# Arduino_extension_connectors.net
KiCad netlist of a schematic drawn in Altium Designer
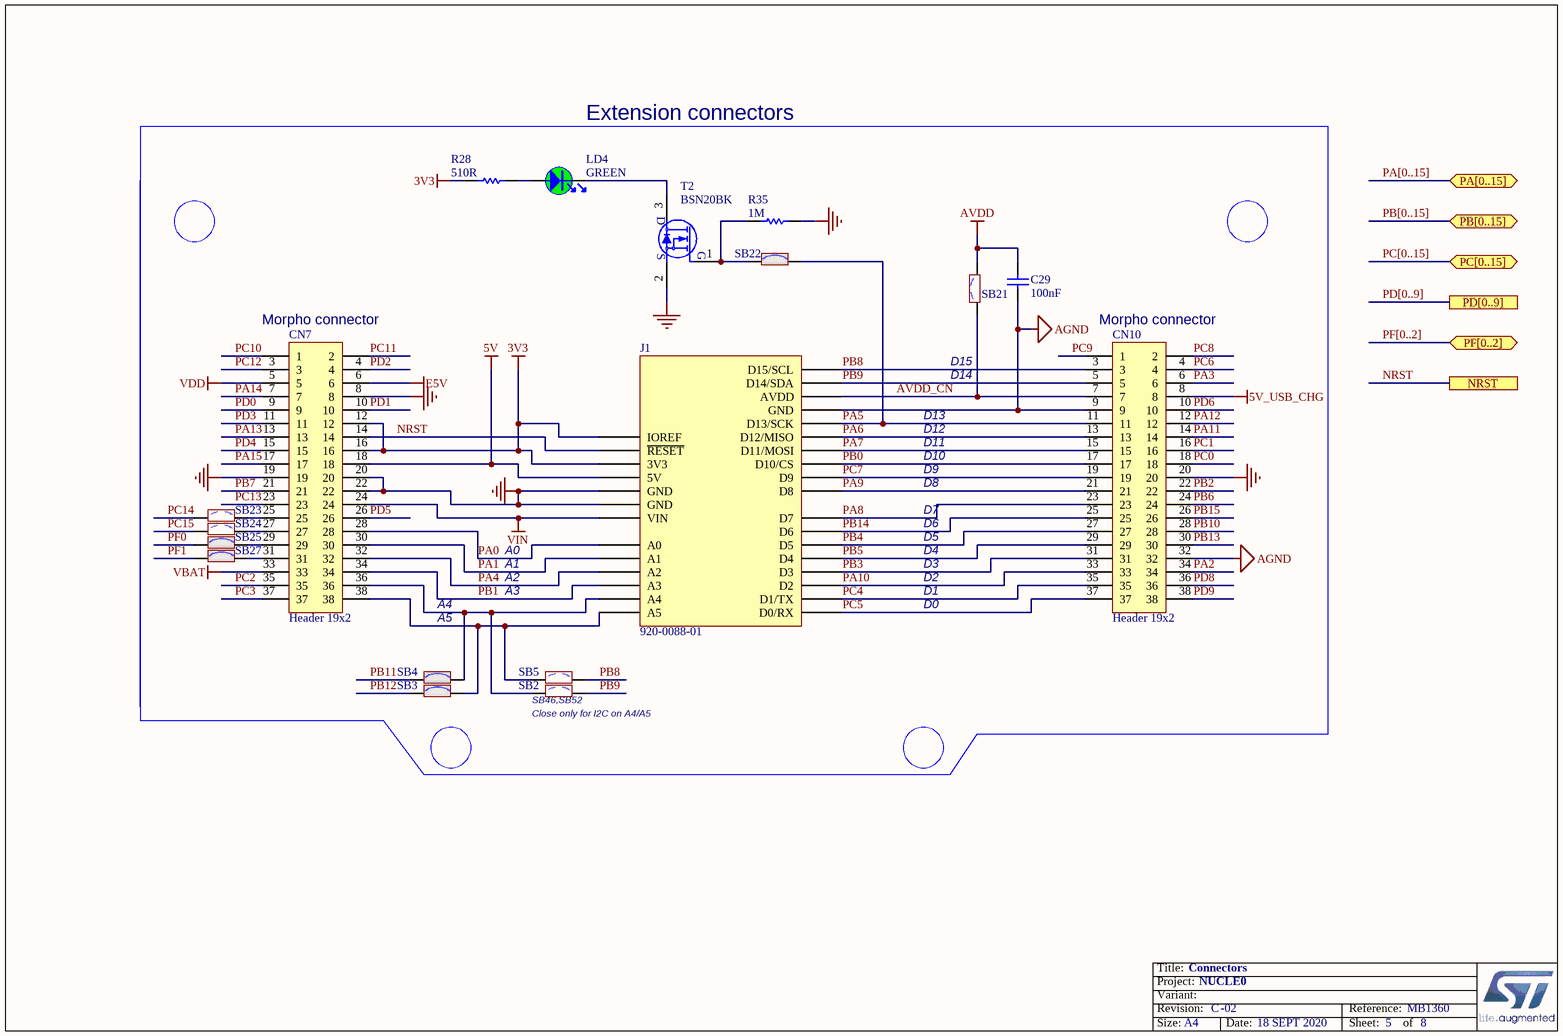
[diagram p0: Arduino_extension_connectors.SchDoc]

(export (version "E")
  (design (tool "Eeschema 10.0.6"))
  (components
    (comp (ref "C29")
      (value "100nF")
      (footprint "C0603")
      (description "Capacitor, MLCC, 100nF, 16V, X7R, 10%, 0603, T=0,8mm")
      (fields
        (field (name "INTERNAL_PART_NUMBER") "MCD-00211")
        (field (name "MANUFACTURER_PART_NUMBER") "CC0603KRX7R7BB104")
        (field (name "PROVIDED_BY") "SUBCO")
      )
      (libsource (lib "MCD_PARTS_database") (part "Capacitor"))
    )
    (comp (ref "CN7")
      (value "Header 19x2")
      (footprint "CON_SAMTEC_TSW-119-09-X-D")
      (description "Header, 19x2, 2,54mm, VR, TH, Height 5.84mm/10.16mm")
      (fields
        (field (name "INTERNAL_PART_NUMBER") "MCD-00213")
        (field (name "MANUFACTURER_PART_NUMBER") "TSW-119-09-x-D")
        (field (name "PROVIDED_BY") "SUBCO")
      )
      (libsource (lib "MCD_PARTS_database") (part "Header 19x2"))
    )
    (comp (ref "CN10")
      (value "Header 19x2")
      (footprint "CON_SAMTEC_TSW-119-09-X-D")
      (description "Header, 19x2, 2,54mm, VR, TH, Height 5.84mm/10.16mm")
      (fields
        (field (name "INTERNAL_PART_NUMBER") "MCD-00213")
        (field (name "MANUFACTURER_PART_NUMBER") "TSW-119-09-x-D")
        (field (name "PROVIDED_BY") "SUBCO")
      )
      (libsource (lib "MCD_PARTS_database") (part "Header 19x2"))
    )
    (comp (ref "J1")
      (value "920-0088-01")
      (footprint "SCHMARTBOARD - 920-0088-01")
      (description "CONN HDR 8/10P 0.1 GOLD PCB 6PC")
      (fields (field (name "MANUFACTURER") "Schmartboard, Inc."))
      (libsource (lib "altiumlibrary.com") (part "Arduino Headers"))
    )
    (comp (ref "LD4")
      (value "GREEN")
      (footprint "LED_0603_GREEN")
      (description "LED, Green, 0603")
      (fields
        (field (name "INTERNAL_PART_NUMBER") "MCD-00050")
        (field (name "MANUFACTURER_PART_NUMBER") "19-213SYGC/S530-E2/TR8")
        (field (name "PROVIDED_BY") "SUBCO")
      )
      (libsource (lib "MCD_PARTS_database") (part "LED_green"))
    )
    (comp (ref "R28")
      (value "510R")
      (footprint "R0603")
      (description "Resistor,510R,0603,1%,1/10W")
      (fields
        (field (name "INTERNAL_PART_NUMBER") "MCD-00225")
        (field (name "MANUFACTURER_PART_NUMBER") "RC0603FR-07510RL")
        (field (name "PROVIDED_BY") "SUBCO")
      )
      (libsource (lib "MCD_PARTS_database") (part "Resistor"))
    )
    (comp (ref "R35")
      (value "1M")
      (footprint "R0603")
      (description "Resistor,1M,0603,1%,1/10W")
      (fields
        (field (name "INTERNAL_PART_NUMBER") "MCD-00257")
        (field (name "MANUFACTURER_PART_NUMBER") "RC0603FR-071ML")
        (field (name "PROVIDED_BY") "SUBCO")
      )
      (libsource (lib "MCD_PARTS_database") (part "Resistor"))
    )
    (comp (ref "SB2")
      (value "SB_OFF")
      (footprint "SOLDER-BRIDGE_R0603-0R")
      (description "Solder Bridge OFF")
      (fields
        (field (name "INTERNAL_PART_NUMBER") "MCD-00072")
        (field (name "MANUFACTURER_PART_NUMBER") "RC0603JR-070RL")
        (field (name "PROVIDED_BY") "SUBCO")
      )
      (libsource (lib "MCD_PARTS_database") (part "SB_OFF"))
    )
    (comp (ref "SB3")
      (value "SB_ON")
      (footprint "SOLDER-BRIDGE_R0603-0R")
      (description "Solder Bridge ON")
      (fields
        (field (name "INTERNAL_PART_NUMBER") "MCD-00071")
        (field (name "MANUFACTURER_PART_NUMBER") "RC0603JR-070RL")
        (field (name "PROVIDED_BY") "SUBCO")
      )
      (libsource (lib "MCD_PARTS_database") (part "SB_ON"))
    )
    (comp (ref "SB4")
      (value "SB_ON")
      (footprint "SOLDER-BRIDGE_R0603-0R")
      (description "Solder Bridge ON")
      (fields
        (field (name "INTERNAL_PART_NUMBER") "MCD-00071")
        (field (name "MANUFACTURER_PART_NUMBER") "RC0603JR-070RL")
        (field (name "PROVIDED_BY") "SUBCO")
      )
      (libsource (lib "MCD_PARTS_database") (part "SB_ON"))
    )
    (comp (ref "SB5")
      (value "SB_OFF")
      (footprint "SOLDER-BRIDGE_R0603-0R")
      (description "Solder Bridge OFF")
      (fields
        (field (name "INTERNAL_PART_NUMBER") "MCD-00072")
        (field (name "MANUFACTURER_PART_NUMBER") "RC0603JR-070RL")
        (field (name "PROVIDED_BY") "SUBCO")
      )
      (libsource (lib "MCD_PARTS_database") (part "SB_OFF"))
    )
    (comp (ref "SB21")
      (value "SB_OFF")
      (footprint "SOLDER-BRIDGE_R0603-0R")
      (description "Solder Bridge OFF")
      (fields
        (field (name "INTERNAL_PART_NUMBER") "MCD-00072")
        (field (name "MANUFACTURER_PART_NUMBER") "RC0603JR-070RL")
        (field (name "PROVIDED_BY") "SUBCO")
      )
      (libsource (lib "") (part "SB_OFF_1"))
    )
    (comp (ref "SB22")
      (value "SB_ON")
      (footprint "SOLDER-BRIDGE_R0603-0R")
      (description "Solder Bridge ON")
      (fields
        (field (name "INTERNAL_PART_NUMBER") "MCD-00071")
        (field (name "MANUFACTURER_PART_NUMBER") "RC0603JR-070RL")
        (field (name "PROVIDED_BY") "SUBCO")
      )
      (libsource (lib "MCD_PARTS_database") (part "SB_ON"))
    )
    (comp (ref "SB23")
      (value "SB_OFF")
      (footprint "SOLDER-BRIDGE_R0603-0R")
      (description "Solder Bridge OFF")
      (fields
        (field (name "INTERNAL_PART_NUMBER") "MCD-00072")
        (field (name "MANUFACTURER_PART_NUMBER") "RC0603JR-070RL")
        (field (name "PROVIDED_BY") "SUBCO")
      )
      (libsource (lib "MCD_PARTS_database") (part "SB_OFF"))
    )
    (comp (ref "SB24")
      (value "SB_OFF")
      (footprint "SOLDER-BRIDGE_R0603-0R")
      (description "Solder Bridge OFF")
      (fields
        (field (name "INTERNAL_PART_NUMBER") "MCD-00072")
        (field (name "MANUFACTURER_PART_NUMBER") "RC0603JR-070RL")
        (field (name "PROVIDED_BY") "SUBCO")
      )
      (libsource (lib "MCD_PARTS_database") (part "SB_OFF"))
    )
    (comp (ref "SB25")
      (value "SB_ON")
      (footprint "SOLDER-BRIDGE_R0603-0R")
      (description "Solder Bridge ON")
      (fields
        (field (name "INTERNAL_PART_NUMBER") "MCD-00071")
        (field (name "MANUFACTURER_PART_NUMBER") "RC0603JR-070RL")
        (field (name "PROVIDED_BY") "SUBCO")
      )
      (libsource (lib "MCD_PARTS_database") (part "SB_ON"))
    )
    (comp (ref "SB27")
      (value "SB_ON")
      (footprint "SOLDER-BRIDGE_R0603-0R")
      (description "Solder Bridge ON")
      (fields
        (field (name "INTERNAL_PART_NUMBER") "MCD-00071")
        (field (name "MANUFACTURER_PART_NUMBER") "RC0603JR-070RL")
        (field (name "PROVIDED_BY") "SUBCO")
      )
      (libsource (lib "MCD_PARTS_database") (part "SB_ON"))
    )
    (comp (ref "T2")
      (value "BSN20BK")
      (footprint "MOS_SOT23")
      (description "N-channel enhancement mode field-effect transistor")
      (fields
        (field (name "INTERNAL_PART_NUMBER") "MCD-01969")
        (field (name "MANUFACTURER") "NEXPERIA")
        (field (name "PROVIDED_BY") "SUBCO")
      )
      (libsource (lib "MCD_PARTS_database") (part "BSN20"))
    )
  )
  (nets
    (net (code "3") (name "/AVDD_CN") (class "Default")
      (node (ref "CN10") (pin "7") (pinfunction "7_7") (pintype "passive"))
      (node (ref "J1") (pin "30") (pinfunction "AVDD_30") (pintype "passive"))
      (node (ref "SB21") (pin "1") (pinfunction "1_1") (pintype "passive"))
    )
    (net (code "4") (name "/NRST") (class "Default")
      (node (ref "CN7") (pin "14") (pinfunction "14_14") (pintype "passive"))
      (node (ref "J1") (pin "3") (pinfunction "~{RESET}_3") (pintype "passive"))
    )
    (net (code "5") (name "/PA0") (class "Default")
      (node (ref "CN7") (pin "28") (pinfunction "28_28") (pintype "passive"))
      (node (ref "J1") (pin "9") (pinfunction "A0_9") (pintype "passive"))
    )
    (net (code "6") (name "/PA1") (class "Default")
      (node (ref "CN7") (pin "30") (pinfunction "30_30") (pintype "passive"))
      (node (ref "J1") (pin "10") (pinfunction "A1_10") (pintype "passive"))
    )
    (net (code "7") (name "/PA2") (class "Default")
      (node (ref "CN10") (pin "34") (pinfunction "34_34") (pintype "passive"))
    )
    (net (code "8") (name "/PA3") (class "Default")
      (node (ref "CN10") (pin "6") (pinfunction "6_6") (pintype "passive"))
    )
    (net (code "9") (name "/PA4") (class "Default")
      (node (ref "CN7") (pin "32") (pinfunction "32_32") (pintype "passive"))
      (node (ref "J1") (pin "11") (pinfunction "A2_11") (pintype "passive"))
    )
    (net (code "10") (name "/PA5") (class "Default")
      (node (ref "CN10") (pin "11") (pinfunction "11_11") (pintype "passive"))
      (node (ref "J1") (pin "28") (pinfunction "D13/SCK_28") (pintype "passive"))
      (node (ref "SB22") (pin "2") (pinfunction "2_2") (pintype "passive"))
    )
    (net (code "11") (name "/PA6") (class "Default")
      (node (ref "CN10") (pin "13") (pinfunction "13_13") (pintype "passive"))
      (node (ref "J1") (pin "27") (pinfunction "D12/MISO_27") (pintype "passive"))
    )
    (net (code "12") (name "/PA7") (class "Default")
      (node (ref "CN10") (pin "15") (pinfunction "15_15") (pintype "passive"))
      (node (ref "J1") (pin "26") (pinfunction "D11/MOSI_26") (pintype "passive"))
    )
    (net (code "13") (name "/PA8") (class "Default")
      (node (ref "CN10") (pin "23") (pinfunction "23_23") (pintype "passive"))
      (node (ref "J1") (pin "22") (pinfunction "D7_22") (pintype "passive"))
    )
    (net (code "14") (name "/PA9") (class "Default")
      (node (ref "CN10") (pin "21") (pinfunction "21_21") (pintype "passive"))
      (node (ref "J1") (pin "23") (pinfunction "D8_23") (pintype "passive"))
    )
    (net (code "15") (name "/PA10") (class "Default")
      (node (ref "CN10") (pin "33") (pinfunction "33_33") (pintype "passive"))
      (node (ref "J1") (pin "17") (pinfunction "D2_17") (pintype "passive"))
    )
    (net (code "16") (name "/PA11") (class "Default")
      (node (ref "CN10") (pin "14") (pinfunction "14_14") (pintype "passive"))
    )
    (net (code "17") (name "/PA12") (class "Default")
      (node (ref "CN10") (pin "12") (pinfunction "12_12") (pintype "passive"))
    )
    (net (code "18") (name "/PA13") (class "Default")
      (node (ref "CN7") (pin "13") (pinfunction "13_13") (pintype "passive"))
    )
    (net (code "19") (name "/PA14") (class "Default")
      (node (ref "CN7") (pin "7") (pinfunction "7_7") (pintype "passive"))
    )
    (net (code "20") (name "/PA15") (class "Default")
      (node (ref "CN7") (pin "17") (pinfunction "17_17") (pintype "passive"))
    )
    (net (code "22") (name "/PB0") (class "Default")
      (node (ref "CN10") (pin "17") (pinfunction "17_17") (pintype "passive"))
      (node (ref "J1") (pin "25") (pinfunction "D10/CS_25") (pintype "passive"))
    )
    (net (code "23") (name "/PB1") (class "Default")
      (node (ref "CN7") (pin "34") (pinfunction "34_34") (pintype "passive"))
      (node (ref "J1") (pin "12") (pinfunction "A3_12") (pintype "passive"))
    )
    (net (code "24") (name "/PB2") (class "Default")
      (node (ref "CN10") (pin "22") (pinfunction "22_22") (pintype "passive"))
    )
    (net (code "25") (name "/PB3") (class "Default")
      (node (ref "CN10") (pin "31") (pinfunction "31_31") (pintype "passive"))
      (node (ref "J1") (pin "18") (pinfunction "D3_18") (pintype "passive"))
    )
    (net (code "26") (name "/PB4") (class "Default")
      (node (ref "CN10") (pin "27") (pinfunction "27_27") (pintype "passive"))
      (node (ref "J1") (pin "20") (pinfunction "D5_20") (pintype "passive"))
    )
    (net (code "27") (name "/PB5") (class "Default")
      (node (ref "CN10") (pin "29") (pinfunction "29_29") (pintype "passive"))
      (node (ref "J1") (pin "19") (pinfunction "D4_19") (pintype "passive"))
    )
    (net (code "28") (name "/PB6") (class "Default")
      (node (ref "CN10") (pin "24") (pinfunction "24_24") (pintype "passive"))
    )
    (net (code "29") (name "/PB7") (class "Default")
      (node (ref "CN7") (pin "21") (pinfunction "21_21") (pintype "passive"))
    )
    (net (code "30") (name "/PB8") (class "Default")
      (node (ref "CN10") (pin "3") (pinfunction "3_3") (pintype "passive"))
      (node (ref "J1") (pin "32") (pinfunction "D15/SCL_32") (pintype "passive"))
      (node (ref "SB5") (pin "2") (pinfunction "2_2") (pintype "passive"))
    )
    (net (code "31") (name "/PB9") (class "Default")
      (node (ref "CN10") (pin "5") (pinfunction "5_5") (pintype "passive"))
      (node (ref "J1") (pin "31") (pinfunction "D14/SDA_31") (pintype "passive"))
      (node (ref "SB2") (pin "2") (pinfunction "2_2") (pintype "passive"))
    )
    (net (code "32") (name "/PB10") (class "Default")
      (node (ref "CN10") (pin "28") (pinfunction "28_28") (pintype "passive"))
    )
    (net (code "33") (name "/PB11") (class "Default")
      (node (ref "SB4") (pin "1") (pinfunction "1_1") (pintype "passive"))
    )
    (net (code "34") (name "/PB12") (class "Default")
      (node (ref "SB3") (pin "1") (pinfunction "1_1") (pintype "passive"))
    )
    (net (code "35") (name "/PB13") (class "Default")
      (node (ref "CN10") (pin "30") (pinfunction "30_30") (pintype "passive"))
    )
    (net (code "36") (name "/PB14") (class "Default")
      (node (ref "CN10") (pin "25") (pinfunction "25_25") (pintype "passive"))
      (node (ref "J1") (pin "21") (pinfunction "D6_21") (pintype "passive"))
    )
    (net (code "37") (name "/PB15") (class "Default")
      (node (ref "CN10") (pin "26") (pinfunction "26_26") (pintype "passive"))
    )
    (net (code "39") (name "/PC0") (class "Default")
      (node (ref "CN10") (pin "18") (pinfunction "18_18") (pintype "passive"))
    )
    (net (code "40") (name "/PC1") (class "Default")
      (node (ref "CN10") (pin "16") (pinfunction "16_16") (pintype "passive"))
    )
    (net (code "41") (name "/PC2") (class "Default")
      (node (ref "CN7") (pin "35") (pinfunction "35_35") (pintype "passive"))
    )
    (net (code "42") (name "/PC3") (class "Default")
      (node (ref "CN7") (pin "37") (pinfunction "37_37") (pintype "passive"))
    )
    (net (code "43") (name "/PC4") (class "Default")
      (node (ref "CN10") (pin "35") (pinfunction "35_35") (pintype "passive"))
      (node (ref "J1") (pin "16") (pinfunction "D1/TX_16") (pintype "passive"))
    )
    (net (code "44") (name "/PC5") (class "Default")
      (node (ref "CN10") (pin "37") (pinfunction "37_37") (pintype "passive"))
      (node (ref "J1") (pin "15") (pinfunction "D0/RX_15") (pintype "passive"))
    )
    (net (code "45") (name "/PC6") (class "Default")
      (node (ref "CN10") (pin "4") (pinfunction "4_4") (pintype "passive"))
    )
    (net (code "46") (name "/PC7") (class "Default")
      (node (ref "CN10") (pin "19") (pinfunction "19_19") (pintype "passive"))
      (node (ref "J1") (pin "24") (pinfunction "D9_24") (pintype "passive"))
    )
    (net (code "47") (name "/PC8") (class "Default")
      (node (ref "CN10") (pin "2") (pinfunction "2_2") (pintype "passive"))
    )
    (net (code "48") (name "/PC9") (class "Default")
      (node (ref "CN10") (pin "1") (pinfunction "1_1") (pintype "passive"))
    )
    (net (code "49") (name "/PC10") (class "Default")
      (node (ref "CN7") (pin "1") (pinfunction "1_1") (pintype "passive"))
    )
    (net (code "50") (name "/PC11") (class "Default")
      (node (ref "CN7") (pin "2") (pinfunction "2_2") (pintype "passive"))
    )
    (net (code "51") (name "/PC12") (class "Default")
      (node (ref "CN7") (pin "3") (pinfunction "3_3") (pintype "passive"))
    )
    (net (code "52") (name "/PC13") (class "Default")
      (node (ref "CN7") (pin "23") (pinfunction "23_23") (pintype "passive"))
    )
    (net (code "53") (name "/PC14") (class "Default")
      (node (ref "SB23") (pin "1") (pinfunction "1_1") (pintype "passive"))
    )
    (net (code "54") (name "/PC15") (class "Default")
      (node (ref "SB24") (pin "1") (pinfunction "1_1") (pintype "passive"))
    )
    (net (code "56") (name "/PD0") (class "Default")
      (node (ref "CN7") (pin "9") (pinfunction "9_9") (pintype "passive"))
    )
    (net (code "57") (name "/PD1") (class "Default")
      (node (ref "CN7") (pin "10") (pinfunction "10_10") (pintype "passive"))
    )
    (net (code "58") (name "/PD2") (class "Default")
      (node (ref "CN7") (pin "4") (pinfunction "4_4") (pintype "passive"))
    )
    (net (code "59") (name "/PD3") (class "Default")
      (node (ref "CN7") (pin "11") (pinfunction "11_11") (pintype "passive"))
    )
    (net (code "60") (name "/PD4") (class "Default")
      (node (ref "CN7") (pin "15") (pinfunction "15_15") (pintype "passive"))
    )
    (net (code "61") (name "/PD5") (class "Default")
      (node (ref "CN7") (pin "26") (pinfunction "26_26") (pintype "passive"))
    )
    (net (code "62") (name "/PD6") (class "Default")
      (node (ref "CN10") (pin "10") (pinfunction "10_10") (pintype "passive"))
    )
    (net (code "63") (name "/PD8") (class "Default")
      (node (ref "CN10") (pin "36") (pinfunction "36_36") (pintype "passive"))
    )
    (net (code "64") (name "/PD9") (class "Default")
      (node (ref "CN10") (pin "38") (pinfunction "38_38") (pintype "passive"))
    )
    (net (code "66") (name "/PF0") (class "Default")
      (node (ref "SB25") (pin "1") (pinfunction "1_1") (pintype "passive"))
    )
    (net (code "67") (name "/PF1") (class "Default")
      (node (ref "SB27") (pin "1") (pinfunction "1_1") (pintype "passive"))
    )
    (net (code "69") (name "3V3") (class "Default")
      (node (ref "CN7") (pin "12") (pinfunction "12_12") (pintype "passive"))
      (node (ref "CN7") (pin "16") (pinfunction "16_16") (pintype "passive"))
      (node (ref "J1") (pin "2") (pinfunction "IOREF_2") (pintype "passive"))
      (node (ref "J1") (pin "4") (pinfunction "3V3_4") (pintype "passive"))
      (node (ref "R28") (pin "2") (pinfunction "2_2") (pintype "passive"))
    )
    (net (code "70") (name "5V") (class "Default")
      (node (ref "CN7") (pin "18") (pinfunction "18_18") (pintype "passive"))
      (node (ref "J1") (pin "5") (pinfunction "5V_5") (pintype "passive"))
    )
    (net (code "71") (name "5V_USB_CHG") (class "Default")
      (node (ref "CN10") (pin "8") (pinfunction "8_8") (pintype "passive"))
    )
    (net (code "72") (name "AGND") (class "Default")
      (node (ref "C29") (pin "1") (pinfunction "1_1") (pintype "passive"))
      (node (ref "CN10") (pin "32") (pinfunction "32_32") (pintype "passive"))
      (node (ref "CN10") (pin "9") (pinfunction "9_9") (pintype "passive"))
      (node (ref "J1") (pin "29") (pinfunction "GND_29") (pintype "passive"))
    )
    (net (code "73") (name "AVDD") (class "Default")
      (node (ref "C29") (pin "2") (pinfunction "2_2") (pintype "passive"))
      (node (ref "SB21") (pin "2") (pinfunction "2_2") (pintype "passive"))
    )
    (net (code "74") (name "E5V") (class "Default")
      (node (ref "CN7") (pin "6") (pinfunction "6_6") (pintype "passive"))
    )
    (net (code "75") (name "GND") (class "Default")
      (node (ref "CN10") (pin "20") (pinfunction "20_20") (pintype "passive"))
      (node (ref "CN7") (pin "19") (pinfunction "19_19") (pintype "passive"))
      (node (ref "CN7") (pin "20") (pinfunction "20_20") (pintype "passive"))
      (node (ref "CN7") (pin "22") (pinfunction "22_22") (pintype "passive"))
      (node (ref "CN7") (pin "8") (pinfunction "8_8") (pintype "passive"))
      (node (ref "J1") (pin "6") (pinfunction "GND_6") (pintype "passive"))
      (node (ref "J1") (pin "7") (pinfunction "GND_7") (pintype "passive"))
      (node (ref "R35") (pin "2") (pinfunction "2_2") (pintype "passive"))
      (node (ref "T2") (pin "2") (pinfunction "S_2") (pintype "passive"))
    )
    (net (code "76") (name "Net-(CN7-Pad25)") (class "Default")
      (node (ref "CN7") (pin "25") (pinfunction "25_25") (pintype "passive"))
      (node (ref "SB23") (pin "2") (pinfunction "2_2") (pintype "passive"))
    )
    (net (code "77") (name "Net-(CN7-Pad27)") (class "Default")
      (node (ref "CN7") (pin "27") (pinfunction "27_27") (pintype "passive"))
      (node (ref "SB24") (pin "2") (pinfunction "2_2") (pintype "passive"))
    )
    (net (code "78") (name "Net-(CN7-Pad29)") (class "Default")
      (node (ref "CN7") (pin "29") (pinfunction "29_29") (pintype "passive"))
      (node (ref "SB25") (pin "2") (pinfunction "2_2") (pintype "passive"))
    )
    (net (code "79") (name "Net-(CN7-Pad31)") (class "Default")
      (node (ref "CN7") (pin "31") (pinfunction "31_31") (pintype "passive"))
      (node (ref "SB27") (pin "2") (pinfunction "2_2") (pintype "passive"))
    )
    (net (code "80") (name "Net-(J1-A4)") (class "Default")
      (node (ref "CN7") (pin "36") (pinfunction "36_36") (pintype "passive"))
      (node (ref "J1") (pin "13") (pinfunction "A4_13") (pintype "passive"))
      (node (ref "SB2") (pin "1") (pinfunction "1_1") (pintype "passive"))
      (node (ref "SB4") (pin "2") (pinfunction "2_2") (pintype "passive"))
    )
    (net (code "81") (name "Net-(J1-A5)") (class "Default")
      (node (ref "CN7") (pin "38") (pinfunction "38_38") (pintype "passive"))
      (node (ref "J1") (pin "14") (pinfunction "A5_14") (pintype "passive"))
      (node (ref "SB3") (pin "2") (pinfunction "2_2") (pintype "passive"))
      (node (ref "SB5") (pin "1") (pinfunction "1_1") (pintype "passive"))
    )
    (net (code "82") (name "Net-(LD4-Pad1)") (class "Default")
      (node (ref "LD4") (pin "1") (pintype "passive"))
      (node (ref "R28") (pin "1") (pinfunction "1_1") (pintype "passive"))
    )
    (net (code "83") (name "Net-(T2-D)") (class "Default")
      (node (ref "LD4") (pin "2") (pintype "passive"))
      (node (ref "T2") (pin "3") (pinfunction "D_3") (pintype "passive"))
    )
    (net (code "84") (name "Net-(T2-G)") (class "Default")
      (node (ref "R35") (pin "1") (pinfunction "1_1") (pintype "passive"))
      (node (ref "SB22") (pin "1") (pinfunction "1_1") (pintype "passive"))
      (node (ref "T2") (pin "1") (pinfunction "G_1") (pintype "passive"))
    )
    (net (code "85") (name "VBAT") (class "Default")
      (node (ref "CN7") (pin "33") (pinfunction "33_33") (pintype "passive"))
    )
    (net (code "86") (name "VDD") (class "Default")
      (node (ref "CN7") (pin "5") (pinfunction "5_5") (pintype "passive"))
    )
    (net (code "87") (name "VIN") (class "Default")
      (node (ref "CN7") (pin "24") (pinfunction "24_24") (pintype "passive"))
      (node (ref "J1") (pin "8") (pinfunction "VIN_8") (pintype "passive"))
    )
  )
)
